# Group_06.net
KiCad netlist of a schematic drawn in EAGLE
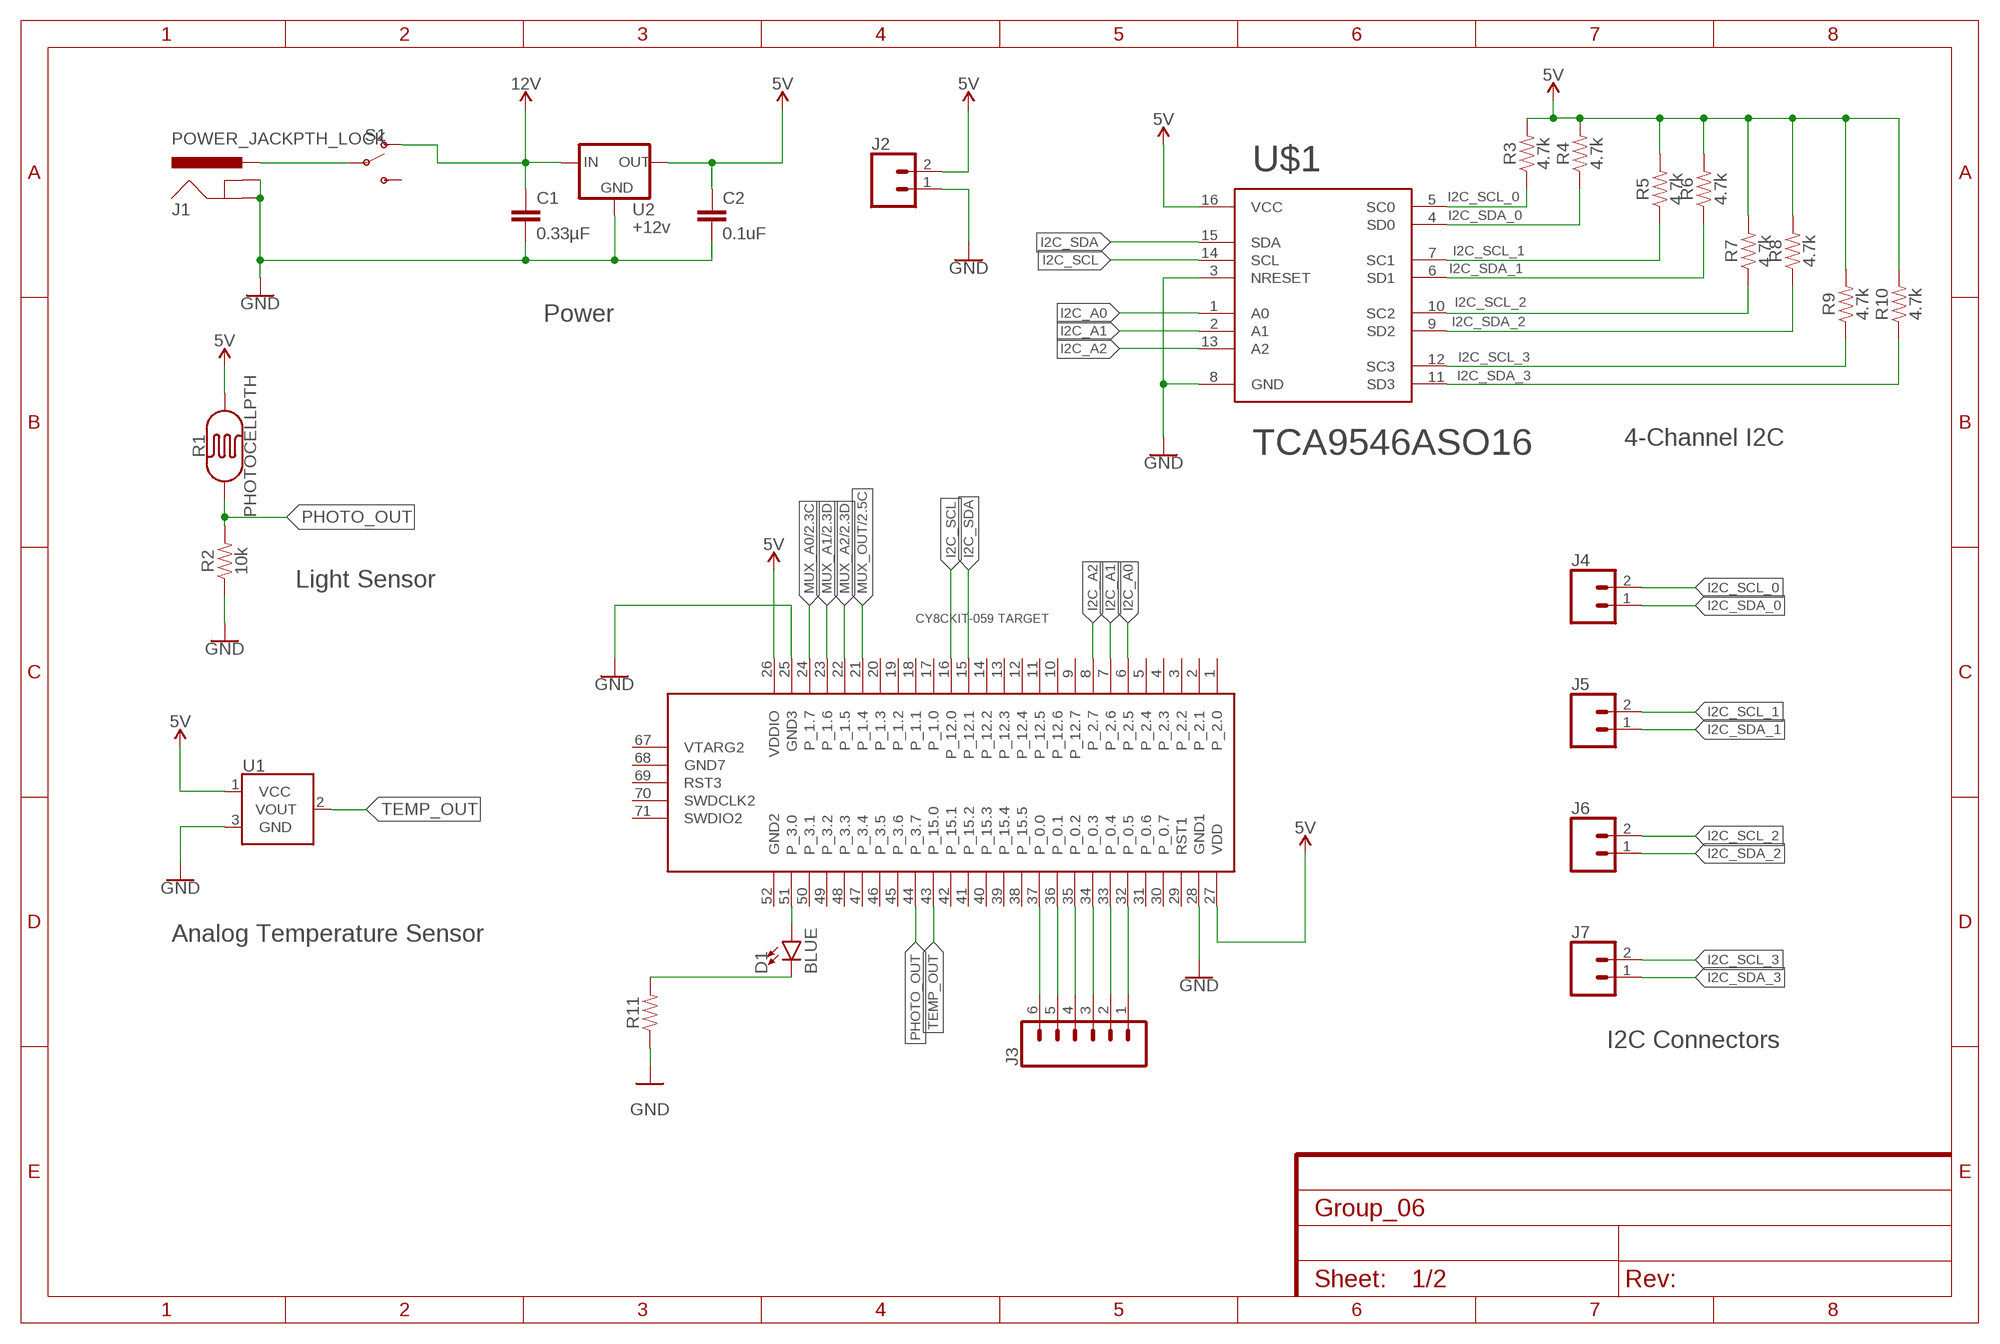
[diagram p0: schematic, sheet 1]
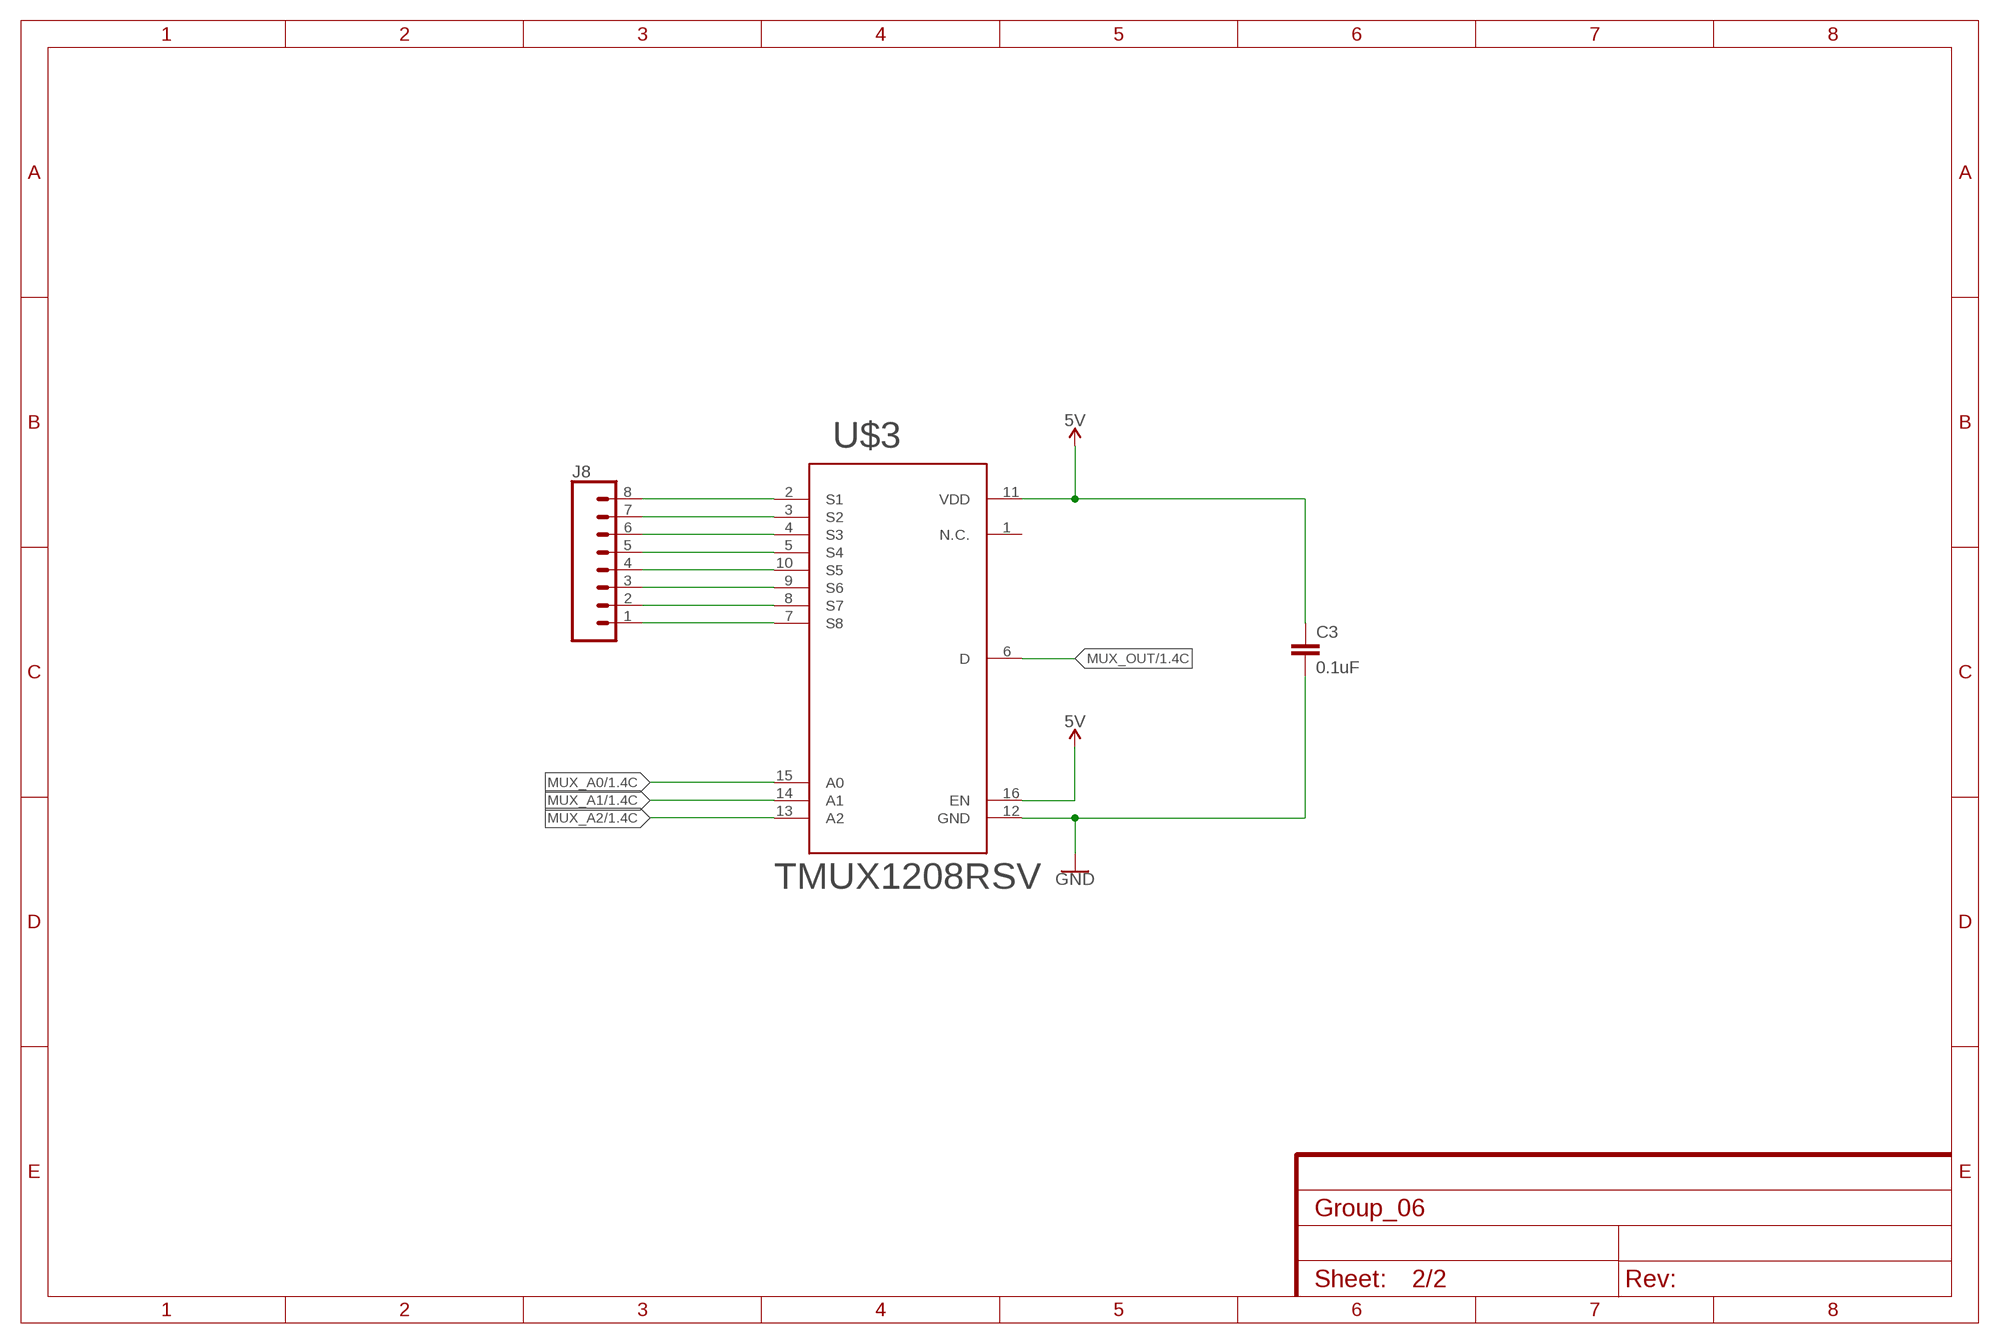
[diagram p1: schematic, sheet 2]

(export (version "E")
  (design (tool "Eeschema 10.0.6"))
  (components
    (comp (ref "C1")
      (value "0.33µF")
      (footprint "eagle-import:0805")
      (libsource (lib "eagle-import") (part "0.33UF/330NF-0805-50V-10%"))
    )
    (comp (ref "C2")
      (value "0.1uF")
      (footprint "eagle-import:CAP-PTH-SMALL-KIT")
      (libsource (lib "eagle-import") (part "0.1UF-KIT-EZ-50V-20%"))
    )
    (comp (ref "D1")
      (value "BLUE")
      (footprint "eagle-import:LED-1206")
      (libsource (lib "eagle-import") (part "LED-BLUE1206"))
    )
    (comp (ref "J1")
      (value "POWER_JACKPTH_LOCK")
      (footprint "eagle-import:POWER_JACK_PTH_LOCK")
      (libsource (lib "eagle-import") (part "POWER_JACKPTH_LOCK"))
    )
    (comp (ref "J2")
      (value "CONN_02")
      (footprint "eagle-import:1X02")
      (libsource (lib "eagle-import") (part "CONN_02"))
    )
    (comp (ref "J3")
      (value "CONN_06LOCK")
      (footprint "eagle-import:1X06_LOCK")
      (libsource (lib "eagle-import") (part "CONN_06LOCK"))
    )
    (comp (ref "J4")
      (value "CONN_02")
      (footprint "eagle-import:1X02")
      (libsource (lib "eagle-import") (part "CONN_02"))
    )
    (comp (ref "J5")
      (value "CONN_02")
      (footprint "eagle-import:1X02")
      (libsource (lib "eagle-import") (part "CONN_02"))
    )
    (comp (ref "J6")
      (value "CONN_02")
      (footprint "eagle-import:1X02")
      (libsource (lib "eagle-import") (part "CONN_02"))
    )
    (comp (ref "J7")
      (value "CONN_02")
      (footprint "eagle-import:1X02")
      (libsource (lib "eagle-import") (part "CONN_02"))
    )
    (comp (ref "R1")
      (value "PHOTOCELLPTH")
      (footprint "eagle-import:PHOTOCELL")
      (libsource (lib "eagle-import") (part "PHOTOCELLPTH"))
    )
    (comp (ref "R2")
      (value "10k")
      (footprint "eagle-import:0603")
      (libsource (lib "eagle-import") (part "10KOHM-0603-1/10W-1%"))
    )
    (comp (ref "R3")
      (value "4.7k")
      (footprint "eagle-import:0603")
      (libsource (lib "eagle-import") (part "4.7KOHM-0603-1/10W-1%"))
    )
    (comp (ref "R4")
      (value "4.7k")
      (footprint "eagle-import:0603")
      (libsource (lib "eagle-import") (part "4.7KOHM-0603-1/10W-1%"))
    )
    (comp (ref "R5")
      (value "4.7k")
      (footprint "eagle-import:0603")
      (libsource (lib "eagle-import") (part "4.7KOHM-0603-1/10W-1%"))
    )
    (comp (ref "R6")
      (value "4.7k")
      (footprint "eagle-import:0603")
      (libsource (lib "eagle-import") (part "4.7KOHM-0603-1/10W-1%"))
    )
    (comp (ref "R7")
      (value "4.7k")
      (footprint "eagle-import:0603")
      (libsource (lib "eagle-import") (part "4.7KOHM-0603-1/10W-1%"))
    )
    (comp (ref "R8")
      (value "4.7k")
      (footprint "eagle-import:0603")
      (libsource (lib "eagle-import") (part "4.7KOHM-0603-1/10W-1%"))
    )
    (comp (ref "R9")
      (value "4.7k")
      (footprint "eagle-import:0603")
      (libsource (lib "eagle-import") (part "4.7KOHM-0603-1/10W-1%"))
    )
    (comp (ref "R10")
      (value "4.7k")
      (footprint "eagle-import:0603")
      (libsource (lib "eagle-import") (part "4.7KOHM-0603-1/10W-1%"))
    )
    (comp (ref "R11")
      (value "RESISTORAXIAL-0.3")
      (footprint "eagle-import:AXIAL-0.3")
      (libsource (lib "eagle-import") (part "RESISTORAXIAL-0.3"))
    )
    (comp (ref "S1")
      (value "SWITCH-SPDT-PTH-11.6X4.0MM")
      (footprint "eagle-import:SWITCH_SPDT_PTH_11.6X4.0MM")
      (libsource (lib "eagle-import") (part "SWITCH-SPDT-PTH-11.6X4.0MM"))
    )
    (comp (ref "U$1")
      (value "TCA9546ASO16")
      (footprint "eagle-import:TSSOP-16")
      (libsource (lib "eagle-import") (part "TCA9546ASO16"))
    )
    (comp (ref "U$2")
      (value "CY8CKIT-059_TARGET")
      (footprint "eagle-import:CY8CKIT-059_TARGET")
      (libsource (lib "eagle-import") (part "CY8CKIT-059_TARGET"))
    )
    (comp (ref "U1")
      (value "TMP36GT9")
      (footprint "eagle-import:TO-92")
      (libsource (lib "eagle-import") (part "TMP36GT9"))
    )
    (comp (ref "U2")
      (value "+12v")
      (footprint "eagle-import:TO-252")
      (libsource (lib "eagle-import") (part "V_REG_78XX7812"))
    )
    (comp (ref "C3")
      (value "0.1uF")
      (footprint "eagle-import:CAP-PTH-SMALL-KIT")
      (libsource (lib "eagle-import") (part "0.1UF-KIT-EZ-50V-20%"))
    )
    (comp (ref "J8")
      (value "CONN_08LOCK")
      (footprint "eagle-import:1X08_LOCK")
      (libsource (lib "eagle-import") (part "CONN_08LOCK"))
    )
    (comp (ref "U$3")
      (value "TMUX1208RSV")
      (footprint "eagle-import:QFN-16")
      (libsource (lib "eagle-import") (part "TMUX1208RSV"))
    )
  )
  (nets
    (net (code "1") (name "5V") (class "Default")
      (node (ref "C2") (pin "1") (pinfunction "1_1") (pintype "passive"))
      (node (ref "C3") (pin "1") (pinfunction "1_1") (pintype "passive"))
      (node (ref "J2") (pin "2") (pinfunction "2_2") (pintype "passive"))
      (node (ref "R1") (pin "2") (pinfunction "P$2_2") (pintype "bidirectional"))
      (node (ref "R10") (pin "2") (pinfunction "2_2") (pintype "passive"))
      (node (ref "R3") (pin "2") (pinfunction "2_2") (pintype "passive"))
      (node (ref "R4") (pin "2") (pinfunction "2_2") (pintype "passive"))
      (node (ref "R5") (pin "2") (pinfunction "2_2") (pintype "passive"))
      (node (ref "R6") (pin "2") (pinfunction "2_2") (pintype "passive"))
      (node (ref "R7") (pin "2") (pinfunction "2_2") (pintype "passive"))
      (node (ref "R8") (pin "2") (pinfunction "2_2") (pintype "passive"))
      (node (ref "R9") (pin "2") (pinfunction "2_2") (pintype "passive"))
      (node (ref "U$1") (pin "16") (pinfunction "VCC_16") (pintype "bidirectional"))
      (node (ref "U$2") (pin "26") (pinfunction "VDDIO_26") (pintype "bidirectional"))
      (node (ref "U$2") (pin "27") (pinfunction "VDD_27") (pintype "bidirectional"))
      (node (ref "U$3") (pin "11") (pinfunction "VDD_11") (pintype "bidirectional"))
      (node (ref "U$3") (pin "16") (pinfunction "EN_16") (pintype "bidirectional"))
      (node (ref "U1") (pin "1") (pinfunction "VCC_1") (pintype "bidirectional"))
      (node (ref "U2") (pin "2") (pinfunction "OUT_2") (pintype "passive"))
    )
    (net (code "2") (name "12V") (class "Default")
      (node (ref "C1") (pin "1") (pinfunction "1_1") (pintype "passive"))
      (node (ref "S1") (pin "1") (pinfunction "O_1") (pintype "passive"))
      (node (ref "U2") (pin "1") (pinfunction "IN_1") (pintype "input"))
    )
    (net (code "3") (name "GND") (class "Default")
      (node (ref "C1") (pin "2") (pinfunction "2_2") (pintype "passive"))
      (node (ref "C2") (pin "2") (pinfunction "2_2") (pintype "passive"))
      (node (ref "C3") (pin "2") (pinfunction "2_2") (pintype "passive"))
      (node (ref "J1") (pin "GND") (pinfunction "GND_GND") (pintype "bidirectional"))
      (node (ref "J1") (pin "GNDBREAK") (pinfunction "GNDBREAK_GNDBREAK") (pintype "bidirectional"))
      (node (ref "J2") (pin "1") (pinfunction "1_1") (pintype "passive"))
      (node (ref "R11") (pin "P$1") (pinfunction "1_P$1") (pintype "passive"))
      (node (ref "R2") (pin "1") (pinfunction "1_1") (pintype "passive"))
      (node (ref "U$1") (pin "3") (pinfunction "NRESET_3") (pintype "bidirectional"))
      (node (ref "U$1") (pin "8") (pinfunction "GND_8") (pintype "bidirectional"))
      (node (ref "U$2") (pin "25") (pinfunction "GND3_25") (pintype "bidirectional"))
      (node (ref "U$2") (pin "28") (pinfunction "GND1_28") (pintype "bidirectional"))
      (node (ref "U$3") (pin "12") (pinfunction "GND_12") (pintype "bidirectional"))
      (node (ref "U1") (pin "3") (pinfunction "GND_3") (pintype "bidirectional"))
      (node (ref "U2") (pin "3") (pinfunction "GND_3") (pintype "input"))
    )
    (net (code "4") (name "I2C_A0") (class "Default")
      (node (ref "U$1") (pin "1") (pinfunction "A0_1") (pintype "bidirectional"))
      (node (ref "U$2") (pin "6") (pinfunction "P_2.5_6") (pintype "bidirectional"))
    )
    (net (code "5") (name "I2C_A1") (class "Default")
      (node (ref "U$1") (pin "2") (pinfunction "A1_2") (pintype "bidirectional"))
      (node (ref "U$2") (pin "7") (pinfunction "P_2.6_7") (pintype "bidirectional"))
    )
    (net (code "6") (name "I2C_A2") (class "Default")
      (node (ref "U$1") (pin "13") (pinfunction "A2_13") (pintype "bidirectional"))
      (node (ref "U$2") (pin "8") (pinfunction "P_2.7_8") (pintype "bidirectional"))
    )
    (net (code "7") (name "I2C_SCL") (class "Default")
      (node (ref "U$1") (pin "14") (pinfunction "SCL_14") (pintype "bidirectional"))
      (node (ref "U$2") (pin "16") (pinfunction "P_12.0_16") (pintype "bidirectional"))
    )
    (net (code "8") (name "I2C_SCL_0") (class "Default")
      (node (ref "J4") (pin "2") (pinfunction "2_2") (pintype "passive"))
      (node (ref "R3") (pin "1") (pinfunction "1_1") (pintype "passive"))
      (node (ref "U$1") (pin "5") (pinfunction "SC0_5") (pintype "bidirectional"))
    )
    (net (code "9") (name "I2C_SCL_1") (class "Default")
      (node (ref "J5") (pin "2") (pinfunction "2_2") (pintype "passive"))
      (node (ref "R5") (pin "1") (pinfunction "1_1") (pintype "passive"))
      (node (ref "U$1") (pin "7") (pinfunction "SC1_7") (pintype "bidirectional"))
    )
    (net (code "10") (name "I2C_SCL_2") (class "Default")
      (node (ref "J6") (pin "2") (pinfunction "2_2") (pintype "passive"))
      (node (ref "R7") (pin "1") (pinfunction "1_1") (pintype "passive"))
      (node (ref "U$1") (pin "10") (pinfunction "SC2_10") (pintype "bidirectional"))
    )
    (net (code "11") (name "I2C_SCL_3") (class "Default")
      (node (ref "J7") (pin "2") (pinfunction "2_2") (pintype "passive"))
      (node (ref "R9") (pin "1") (pinfunction "1_1") (pintype "passive"))
      (node (ref "U$1") (pin "12") (pinfunction "SC3_12") (pintype "bidirectional"))
    )
    (net (code "12") (name "I2C_SDA") (class "Default")
      (node (ref "U$1") (pin "15") (pinfunction "SDA_15") (pintype "bidirectional"))
      (node (ref "U$2") (pin "15") (pinfunction "P_12.1_15") (pintype "bidirectional"))
    )
    (net (code "13") (name "I2C_SDA_0") (class "Default")
      (node (ref "J4") (pin "1") (pinfunction "1_1") (pintype "passive"))
      (node (ref "R4") (pin "1") (pinfunction "1_1") (pintype "passive"))
      (node (ref "U$1") (pin "4") (pinfunction "SD0_4") (pintype "bidirectional"))
    )
    (net (code "14") (name "I2C_SDA_1") (class "Default")
      (node (ref "J5") (pin "1") (pinfunction "1_1") (pintype "passive"))
      (node (ref "R6") (pin "1") (pinfunction "1_1") (pintype "passive"))
      (node (ref "U$1") (pin "6") (pinfunction "SD1_6") (pintype "bidirectional"))
    )
    (net (code "15") (name "I2C_SDA_2") (class "Default")
      (node (ref "J6") (pin "1") (pinfunction "1_1") (pintype "passive"))
      (node (ref "R8") (pin "1") (pinfunction "1_1") (pintype "passive"))
      (node (ref "U$1") (pin "9") (pinfunction "SD2_9") (pintype "bidirectional"))
    )
    (net (code "16") (name "I2C_SDA_3") (class "Default")
      (node (ref "J7") (pin "1") (pinfunction "1_1") (pintype "passive"))
      (node (ref "R10") (pin "1") (pinfunction "1_1") (pintype "passive"))
      (node (ref "U$1") (pin "11") (pinfunction "SD3_11") (pintype "bidirectional"))
    )
    (net (code "17") (name "MUX_A0") (class "Default")
      (node (ref "U$2") (pin "24") (pinfunction "P_1.7_24") (pintype "bidirectional"))
      (node (ref "U$3") (pin "15") (pinfunction "A0_15") (pintype "bidirectional"))
    )
    (net (code "18") (name "MUX_A1") (class "Default")
      (node (ref "U$2") (pin "23") (pinfunction "P_1.6_23") (pintype "bidirectional"))
      (node (ref "U$3") (pin "14") (pinfunction "A1_14") (pintype "bidirectional"))
    )
    (net (code "19") (name "MUX_A2") (class "Default")
      (node (ref "U$2") (pin "22") (pinfunction "P_1.5_22") (pintype "bidirectional"))
      (node (ref "U$3") (pin "13") (pinfunction "A2_13") (pintype "bidirectional"))
    )
    (net (code "20") (name "MUX_OUT") (class "Default")
      (node (ref "U$2") (pin "21") (pinfunction "P_1.4_21") (pintype "bidirectional"))
      (node (ref "U$3") (pin "6") (pinfunction "D_6") (pintype "bidirectional"))
    )
    (net (code "21") (name "Net-(R11-2)") (class "Default")
      (node (ref "D1") (pin "C") (pinfunction "C_C") (pintype "passive"))
      (node (ref "R11") (pin "P$2") (pinfunction "2_P$2") (pintype "passive"))
    )
    (net (code "22") (name "Net-(S1-P)") (class "Default")
      (node (ref "J1") (pin "PWR") (pinfunction "PWR_PWR") (pintype "bidirectional"))
      (node (ref "S1") (pin "2") (pinfunction "P_2") (pintype "passive"))
    )
    (net (code "23") (name "Net-(U$2-P_0.0)") (class "Default")
      (node (ref "J3") (pin "6") (pinfunction "6_6") (pintype "passive"))
      (node (ref "U$2") (pin "37") (pinfunction "P_0.0_37") (pintype "bidirectional"))
    )
    (net (code "24") (name "Net-(U$2-P_0.1)") (class "Default")
      (node (ref "J3") (pin "5") (pinfunction "5_5") (pintype "passive"))
      (node (ref "U$2") (pin "36") (pinfunction "P_0.1_36") (pintype "bidirectional"))
    )
    (net (code "25") (name "Net-(U$2-P_0.2)") (class "Default")
      (node (ref "J3") (pin "4") (pinfunction "4_4") (pintype "passive"))
      (node (ref "U$2") (pin "35") (pinfunction "P_0.2_35") (pintype "bidirectional"))
    )
    (net (code "26") (name "Net-(U$2-P_0.3)") (class "Default")
      (node (ref "J3") (pin "3") (pinfunction "3_3") (pintype "passive"))
      (node (ref "U$2") (pin "34") (pinfunction "P_0.3_34") (pintype "bidirectional"))
    )
    (net (code "27") (name "Net-(U$2-P_0.4)") (class "Default")
      (node (ref "J3") (pin "2") (pinfunction "2_2") (pintype "passive"))
      (node (ref "U$2") (pin "33") (pinfunction "P_0.4_33") (pintype "bidirectional"))
    )
    (net (code "28") (name "Net-(U$2-P_0.5)") (class "Default")
      (node (ref "J3") (pin "1") (pinfunction "1_1") (pintype "passive"))
      (node (ref "U$2") (pin "32") (pinfunction "P_0.5_32") (pintype "bidirectional"))
    )
    (net (code "29") (name "Net-(U$2-P_3.0)") (class "Default")
      (node (ref "D1") (pin "A") (pinfunction "A_A") (pintype "passive"))
      (node (ref "U$2") (pin "51") (pinfunction "P_3.0_51") (pintype "bidirectional"))
    )
    (net (code "30") (name "Net-(U$3-S1)") (class "Default")
      (node (ref "J8") (pin "8") (pinfunction "8_8") (pintype "passive"))
      (node (ref "U$3") (pin "2") (pinfunction "S1_2") (pintype "bidirectional"))
    )
    (net (code "31") (name "Net-(U$3-S2)") (class "Default")
      (node (ref "J8") (pin "7") (pinfunction "7_7") (pintype "passive"))
      (node (ref "U$3") (pin "3") (pinfunction "S2_3") (pintype "bidirectional"))
    )
    (net (code "32") (name "Net-(U$3-S3)") (class "Default")
      (node (ref "J8") (pin "6") (pinfunction "6_6") (pintype "passive"))
      (node (ref "U$3") (pin "4") (pinfunction "S3_4") (pintype "bidirectional"))
    )
    (net (code "33") (name "Net-(U$3-S4)") (class "Default")
      (node (ref "J8") (pin "5") (pinfunction "5_5") (pintype "passive"))
      (node (ref "U$3") (pin "5") (pinfunction "S4_5") (pintype "bidirectional"))
    )
    (net (code "34") (name "Net-(U$3-S5)") (class "Default")
      (node (ref "J8") (pin "4") (pinfunction "4_4") (pintype "passive"))
      (node (ref "U$3") (pin "10") (pinfunction "S5_10") (pintype "bidirectional"))
    )
    (net (code "35") (name "Net-(U$3-S6)") (class "Default")
      (node (ref "J8") (pin "3") (pinfunction "3_3") (pintype "passive"))
      (node (ref "U$3") (pin "9") (pinfunction "S6_9") (pintype "bidirectional"))
    )
    (net (code "36") (name "Net-(U$3-S7)") (class "Default")
      (node (ref "J8") (pin "2") (pinfunction "2_2") (pintype "passive"))
      (node (ref "U$3") (pin "8") (pinfunction "S7_8") (pintype "bidirectional"))
    )
    (net (code "37") (name "Net-(U$3-S8)") (class "Default")
      (node (ref "J8") (pin "1") (pinfunction "1_1") (pintype "passive"))
      (node (ref "U$3") (pin "7") (pinfunction "S8_7") (pintype "bidirectional"))
    )
    (net (code "38") (name "PHOTO_OUT") (class "Default")
      (node (ref "R1") (pin "1") (pinfunction "P$1_1") (pintype "bidirectional"))
      (node (ref "R2") (pin "2") (pinfunction "2_2") (pintype "passive"))
      (node (ref "U$2") (pin "44") (pinfunction "P_3.7_44") (pintype "bidirectional"))
    )
    (net (code "39") (name "TEMP_OUT") (class "Default")
      (node (ref "U$2") (pin "43") (pinfunction "P_15.0_43") (pintype "bidirectional"))
      (node (ref "U1") (pin "2") (pinfunction "VOUT_2") (pintype "bidirectional"))
    )
    (net (code "40") (name "unconnected-(S1-S-Pad3)") (class "Default")
      (node (ref "S1") (pin "3") (pinfunction "S_3") (pintype "passive"))
    )
    (net (code "41") (name "unconnected-(U$2-GND2-Pad52)") (class "Default")
      (node (ref "U$2") (pin "52") (pinfunction "GND2_52") (pintype "bidirectional"))
    )
    (net (code "42") (name "unconnected-(U$2-GND7-Pad68)") (class "Default")
      (node (ref "U$2") (pin "68") (pinfunction "GND7_68") (pintype "bidirectional"))
    )
    (net (code "43") (name "unconnected-(U$2-P_0.6-Pad31)") (class "Default")
      (node (ref "U$2") (pin "31") (pinfunction "P_0.6_31") (pintype "bidirectional"))
    )
    (net (code "44") (name "unconnected-(U$2-P_0.7-Pad30)") (class "Default")
      (node (ref "U$2") (pin "30") (pinfunction "P_0.7_30") (pintype "bidirectional"))
    )
    (net (code "45") (name "unconnected-(U$2-P_1.0-Pad17)") (class "Default")
      (node (ref "U$2") (pin "17") (pinfunction "P_1.0_17") (pintype "bidirectional"))
    )
    (net (code "46") (name "unconnected-(U$2-P_1.1-Pad18)") (class "Default")
      (node (ref "U$2") (pin "18") (pinfunction "P_1.1_18") (pintype "bidirectional"))
    )
    (net (code "47") (name "unconnected-(U$2-P_1.2-Pad19)") (class "Default")
      (node (ref "U$2") (pin "19") (pinfunction "P_1.2_19") (pintype "bidirectional"))
    )
    (net (code "48") (name "unconnected-(U$2-P_1.3-Pad20)") (class "Default")
      (node (ref "U$2") (pin "20") (pinfunction "P_1.3_20") (pintype "bidirectional"))
    )
    (net (code "49") (name "unconnected-(U$2-P_2.0-Pad1)") (class "Default")
      (node (ref "U$2") (pin "1") (pinfunction "P_2.0_1") (pintype "bidirectional"))
    )
    (net (code "50") (name "unconnected-(U$2-P_2.1-Pad2)") (class "Default")
      (node (ref "U$2") (pin "2") (pinfunction "P_2.1_2") (pintype "bidirectional"))
    )
    (net (code "51") (name "unconnected-(U$2-P_2.2-Pad3)") (class "Default")
      (node (ref "U$2") (pin "3") (pinfunction "P_2.2_3") (pintype "bidirectional"))
    )
    (net (code "52") (name "unconnected-(U$2-P_2.3-Pad4)") (class "Default")
      (node (ref "U$2") (pin "4") (pinfunction "P_2.3_4") (pintype "bidirectional"))
    )
    (net (code "53") (name "unconnected-(U$2-P_2.4-Pad5)") (class "Default")
      (node (ref "U$2") (pin "5") (pinfunction "P_2.4_5") (pintype "bidirectional"))
    )
    (net (code "54") (name "unconnected-(U$2-P_3.1-Pad50)") (class "Default")
      (node (ref "U$2") (pin "50") (pinfunction "P_3.1_50") (pintype "bidirectional"))
    )
    (net (code "55") (name "unconnected-(U$2-P_3.2-Pad49)") (class "Default")
      (node (ref "U$2") (pin "49") (pinfunction "P_3.2_49") (pintype "bidirectional"))
    )
    (net (code "56") (name "unconnected-(U$2-P_3.3-Pad48)") (class "Default")
      (node (ref "U$2") (pin "48") (pinfunction "P_3.3_48") (pintype "bidirectional"))
    )
    (net (code "57") (name "unconnected-(U$2-P_3.4-Pad47)") (class "Default")
      (node (ref "U$2") (pin "47") (pinfunction "P_3.4_47") (pintype "bidirectional"))
    )
    (net (code "58") (name "unconnected-(U$2-P_3.5-Pad46)") (class "Default")
      (node (ref "U$2") (pin "46") (pinfunction "P_3.5_46") (pintype "bidirectional"))
    )
    (net (code "59") (name "unconnected-(U$2-P_3.6-Pad45)") (class "Default")
      (node (ref "U$2") (pin "45") (pinfunction "P_3.6_45") (pintype "bidirectional"))
    )
    (net (code "60") (name "unconnected-(U$2-P_12.2-Pad14)") (class "Default")
      (node (ref "U$2") (pin "14") (pinfunction "P_12.2_14") (pintype "bidirectional"))
    )
    (net (code "61") (name "unconnected-(U$2-P_12.3-Pad13)") (class "Default")
      (node (ref "U$2") (pin "13") (pinfunction "P_12.3_13") (pintype "bidirectional"))
    )
    (net (code "62") (name "unconnected-(U$2-P_12.4-Pad12)") (class "Default")
      (node (ref "U$2") (pin "12") (pinfunction "P_12.4_12") (pintype "bidirectional"))
    )
    (net (code "63") (name "unconnected-(U$2-P_12.5-Pad11)") (class "Default")
      (node (ref "U$2") (pin "11") (pinfunction "P_12.5_11") (pintype "bidirectional"))
    )
    (net (code "64") (name "unconnected-(U$2-P_12.6-Pad10)") (class "Default")
      (node (ref "U$2") (pin "10") (pinfunction "P_12.6_10") (pintype "bidirectional"))
    )
    (net (code "65") (name "unconnected-(U$2-P_12.7-Pad9)") (class "Default")
      (node (ref "U$2") (pin "9") (pinfunction "P_12.7_9") (pintype "bidirectional"))
    )
    (net (code "66") (name "unconnected-(U$2-P_15.1-Pad42)") (class "Default")
      (node (ref "U$2") (pin "42") (pinfunction "P_15.1_42") (pintype "bidirectional"))
    )
    (net (code "67") (name "unconnected-(U$2-P_15.2-Pad41)") (class "Default")
      (node (ref "U$2") (pin "41") (pinfunction "P_15.2_41") (pintype "bidirectional"))
    )
    (net (code "68") (name "unconnected-(U$2-P_15.3-Pad40)") (class "Default")
      (node (ref "U$2") (pin "40") (pinfunction "P_15.3_40") (pintype "bidirectional"))
    )
    (net (code "69") (name "unconnected-(U$2-P_15.4-Pad39)") (class "Default")
      (node (ref "U$2") (pin "39") (pinfunction "P_15.4_39") (pintype "bidirectional"))
    )
    (net (code "70") (name "unconnected-(U$2-P_15.5-Pad38)") (class "Default")
      (node (ref "U$2") (pin "38") (pinfunction "P_15.5_38") (pintype "bidirectional"))
    )
    (net (code "71") (name "unconnected-(U$2-RST1-Pad29)") (class "Default")
      (node (ref "U$2") (pin "29") (pinfunction "RST1_29") (pintype "bidirectional"))
    )
    (net (code "72") (name "unconnected-(U$2-RST3-Pad69)") (class "Default")
      (node (ref "U$2") (pin "69") (pinfunction "RST3_69") (pintype "bidirectional"))
    )
    (net (code "73") (name "unconnected-(U$2-SWDCLK2-Pad70)") (class "Default")
      (node (ref "U$2") (pin "70") (pinfunction "SWDCLK2_70") (pintype "bidirectional"))
    )
    (net (code "74") (name "unconnected-(U$2-SWDIO2-Pad71)") (class "Default")
      (node (ref "U$2") (pin "71") (pinfunction "SWDIO2_71") (pintype "bidirectional"))
    )
    (net (code "75") (name "unconnected-(U$2-VTARG2-Pad67)") (class "Default")
      (node (ref "U$2") (pin "67") (pinfunction "VTARG2_67") (pintype "bidirectional"))
    )
    (net (code "76") (name "unconnected-(U$3-N.C.-Pad1)") (class "Default")
      (node (ref "U$3") (pin "1") (pinfunction "N.C._1") (pintype "bidirectional"))
    )
  )
)
